# 09-DPLL-3.net
KiCad netlist of a schematic drawn in Altium Designer
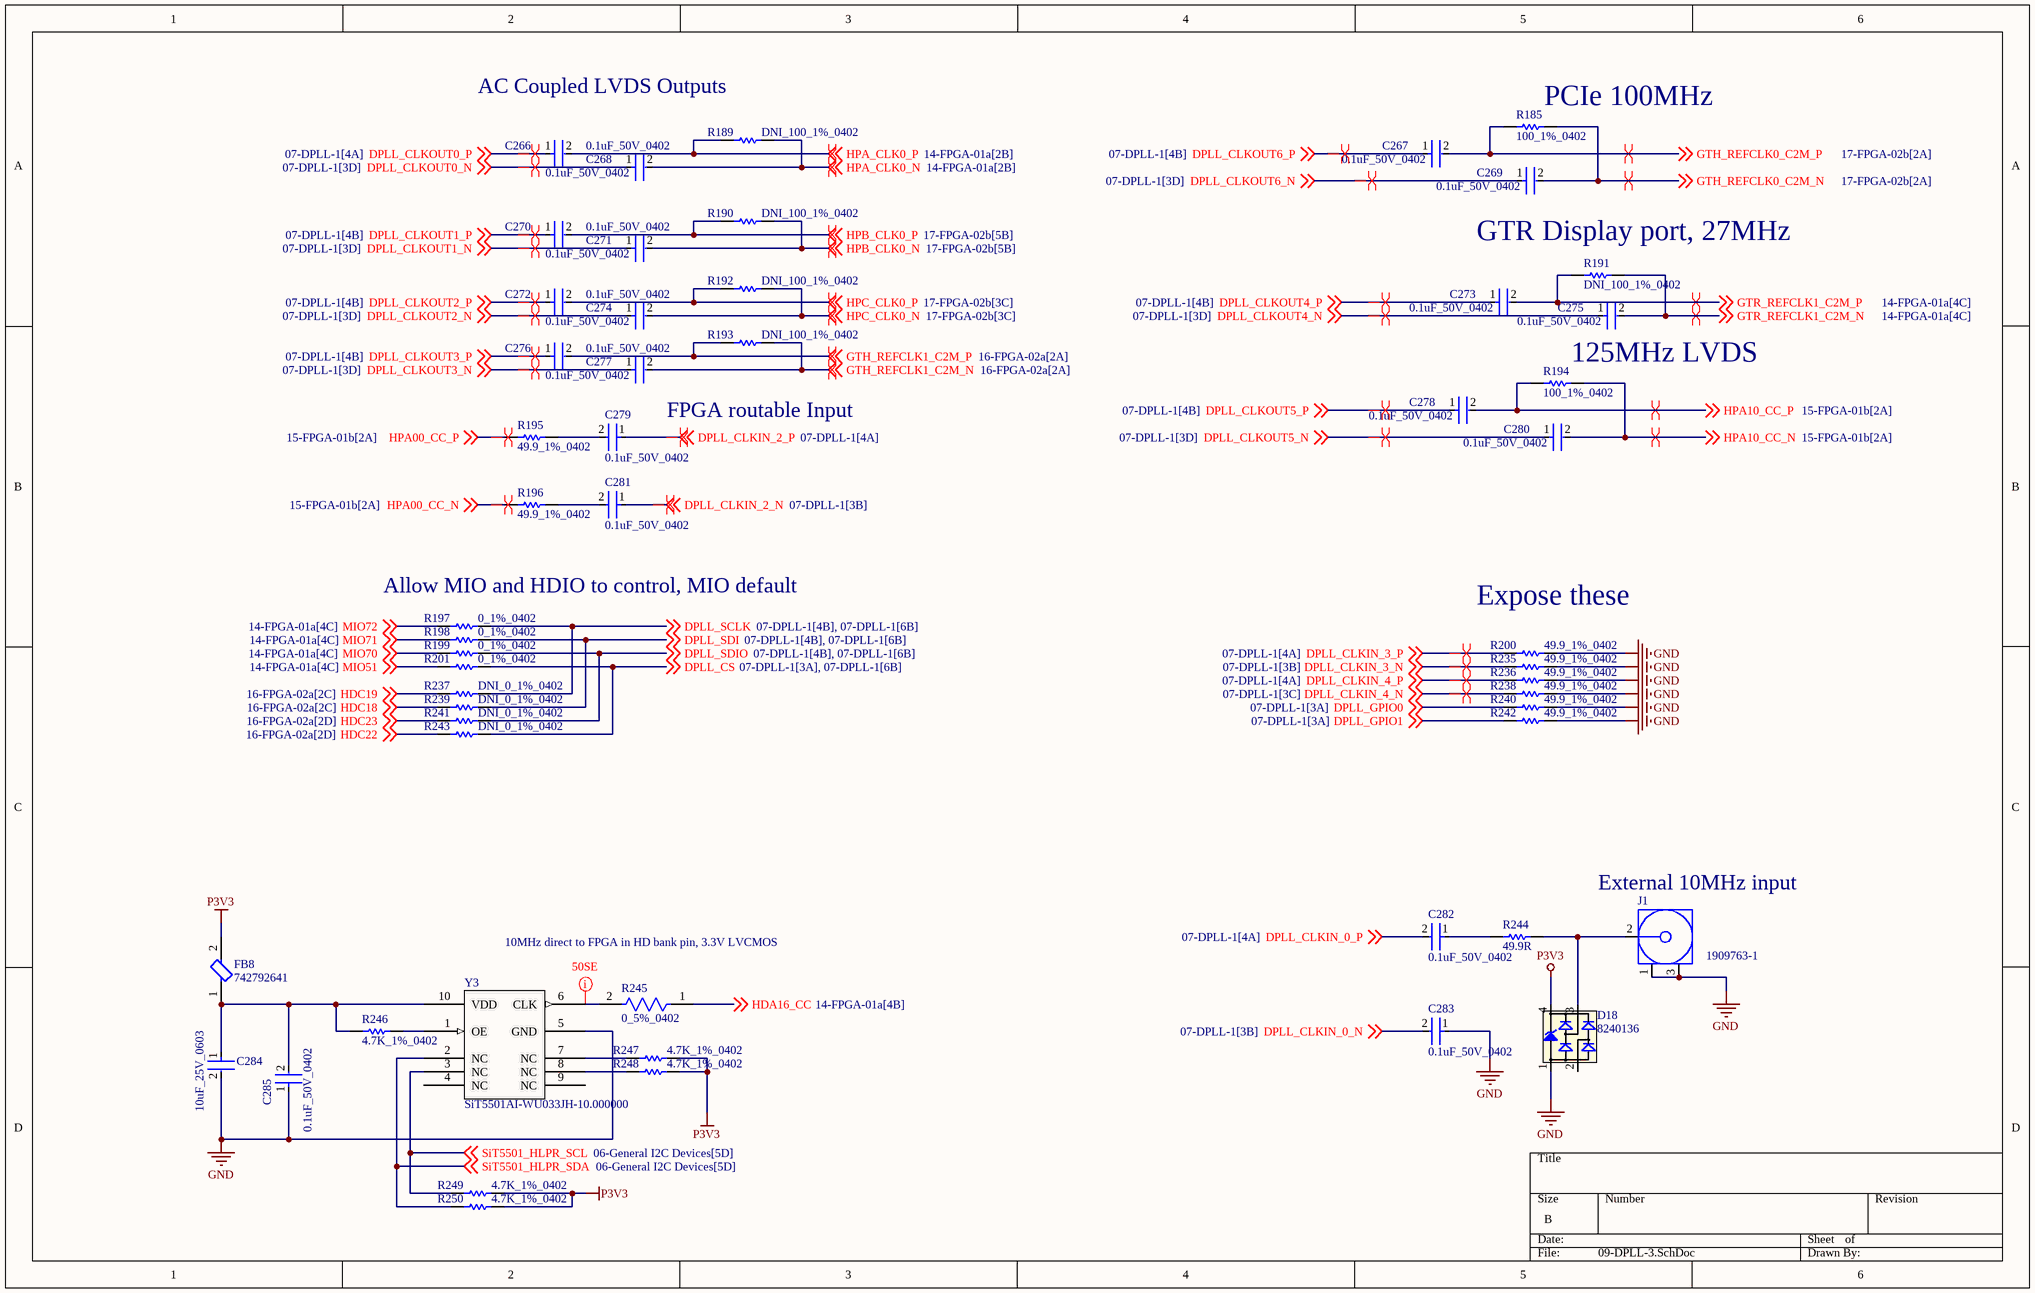
[diagram p0: 09-DPLL-3.SchDoc]

(export (version "E")
  (design (tool "Eeschema 10.0.6"))
  (components
    (comp (ref "C266")
      (value "0.1uF_50V_0402")
      (footprint "FP-C1005-050-0_05-IPC_C")
      (description "Multilayer Ceramic Capacitors 100nF ±10% 50V X7R SMD 0402")
      (fields (field (name "VOLTAGE") "50V") (field (name "TOLERANCE") "10%"))
      (libsource (lib "Altium Content Vault") (part "b4654b650e69147ec39a6b967a45e02"))
    )
    (comp (ref "C267")
      (value "0.1uF_50V_0402")
      (footprint "FP-C1005-050-0_05-IPC_C")
      (description "Multilayer Ceramic Capacitors 100nF ±10% 50V X7R SMD 0402")
      (fields (field (name "VOLTAGE") "50V") (field (name "TOLERANCE") "10%"))
      (libsource (lib "Altium Content Vault") (part "b4654b650e69147ec39a6b967a45e02"))
    )
    (comp (ref "C268")
      (value "0.1uF_50V_0402")
      (footprint "FP-C1005-050-0_05-IPC_C")
      (description "Multilayer Ceramic Capacitors 100nF ±10% 50V X7R SMD 0402")
      (fields (field (name "VOLTAGE") "50V") (field (name "TOLERANCE") "10%"))
      (libsource (lib "Altium Content Vault") (part "b4654b650e69147ec39a6b967a45e02"))
    )
    (comp (ref "C269")
      (value "0.1uF_50V_0402")
      (footprint "FP-C1005-050-0_05-IPC_C")
      (description "Multilayer Ceramic Capacitors 100nF ±10% 50V X7R SMD 0402")
      (fields (field (name "VOLTAGE") "50V") (field (name "TOLERANCE") "10%"))
      (libsource (lib "Altium Content Vault") (part "b4654b650e69147ec39a6b967a45e02"))
    )
    (comp (ref "C270")
      (value "0.1uF_50V_0402")
      (footprint "FP-C1005-050-0_05-IPC_C")
      (description "Multilayer Ceramic Capacitors 100nF ±10% 50V X7R SMD 0402")
      (fields (field (name "VOLTAGE") "50V") (field (name "TOLERANCE") "10%"))
      (libsource (lib "Altium Content Vault") (part "b4654b650e69147ec39a6b967a45e02"))
    )
    (comp (ref "C271")
      (value "0.1uF_50V_0402")
      (footprint "FP-C1005-050-0_05-IPC_C")
      (description "Multilayer Ceramic Capacitors 100nF ±10% 50V X7R SMD 0402")
      (fields (field (name "VOLTAGE") "50V") (field (name "TOLERANCE") "10%"))
      (libsource (lib "Altium Content Vault") (part "b4654b650e69147ec39a6b967a45e02"))
    )
    (comp (ref "C272")
      (value "0.1uF_50V_0402")
      (footprint "FP-C1005-050-0_05-IPC_C")
      (description "Multilayer Ceramic Capacitors 100nF ±10% 50V X7R SMD 0402")
      (fields (field (name "VOLTAGE") "50V") (field (name "TOLERANCE") "10%"))
      (libsource (lib "Altium Content Vault") (part "b4654b650e69147ec39a6b967a45e02"))
    )
    (comp (ref "C273")
      (value "0.1uF_50V_0402")
      (footprint "FP-C1005-050-0_05-IPC_C")
      (description "Multilayer Ceramic Capacitors 100nF ±10% 50V X7R SMD 0402")
      (fields (field (name "VOLTAGE") "50V") (field (name "TOLERANCE") "10%"))
      (libsource (lib "Altium Content Vault") (part "b4654b650e69147ec39a6b967a45e02"))
    )
    (comp (ref "C274")
      (value "0.1uF_50V_0402")
      (footprint "FP-C1005-050-0_05-IPC_C")
      (description "Multilayer Ceramic Capacitors 100nF ±10% 50V X7R SMD 0402")
      (fields (field (name "VOLTAGE") "50V") (field (name "TOLERANCE") "10%"))
      (libsource (lib "Altium Content Vault") (part "b4654b650e69147ec39a6b967a45e02"))
    )
    (comp (ref "C275")
      (value "0.1uF_50V_0402")
      (footprint "FP-C1005-050-0_05-IPC_C")
      (description "Multilayer Ceramic Capacitors 100nF ±10% 50V X7R SMD 0402")
      (fields (field (name "VOLTAGE") "50V") (field (name "TOLERANCE") "10%"))
      (libsource (lib "Altium Content Vault") (part "b4654b650e69147ec39a6b967a45e02"))
    )
    (comp (ref "C276")
      (value "0.1uF_50V_0402")
      (footprint "FP-C1005-050-0_05-IPC_C")
      (description "Multilayer Ceramic Capacitors 100nF ±10% 50V X7R SMD 0402")
      (fields (field (name "VOLTAGE") "50V") (field (name "TOLERANCE") "10%"))
      (libsource (lib "Altium Content Vault") (part "b4654b650e69147ec39a6b967a45e02"))
    )
    (comp (ref "C277")
      (value "0.1uF_50V_0402")
      (footprint "FP-C1005-050-0_05-IPC_C")
      (description "Multilayer Ceramic Capacitors 100nF ±10% 50V X7R SMD 0402")
      (fields (field (name "VOLTAGE") "50V") (field (name "TOLERANCE") "10%"))
      (libsource (lib "Altium Content Vault") (part "b4654b650e69147ec39a6b967a45e02"))
    )
    (comp (ref "C278")
      (value "0.1uF_50V_0402")
      (footprint "FP-C1005-050-0_05-IPC_C")
      (description "Multilayer Ceramic Capacitors 100nF ±10% 50V X7R SMD 0402")
      (fields (field (name "VOLTAGE") "50V") (field (name "TOLERANCE") "10%"))
      (libsource (lib "Altium Content Vault") (part "b4654b650e69147ec39a6b967a45e02"))
    )
    (comp (ref "C279")
      (value "0.1uF_50V_0402")
      (footprint "FP-C1005-050-0_05-IPC_C")
      (description "Multilayer Ceramic Capacitors 100nF ±10% 50V X7R SMD 0402")
      (fields (field (name "VOLTAGE") "50V") (field (name "TOLERANCE") "10%"))
      (libsource (lib "Altium Content Vault") (part "b4654b650e69147ec39a6b967a45e02"))
    )
    (comp (ref "C280")
      (value "0.1uF_50V_0402")
      (footprint "FP-C1005-050-0_05-IPC_C")
      (description "Multilayer Ceramic Capacitors 100nF ±10% 50V X7R SMD 0402")
      (fields (field (name "VOLTAGE") "50V") (field (name "TOLERANCE") "10%"))
      (libsource (lib "Altium Content Vault") (part "b4654b650e69147ec39a6b967a45e02"))
    )
    (comp (ref "C281")
      (value "0.1uF_50V_0402")
      (footprint "FP-C1005-050-0_05-IPC_C")
      (description "Multilayer Ceramic Capacitors 100nF ±10% 50V X7R SMD 0402")
      (fields (field (name "VOLTAGE") "50V") (field (name "TOLERANCE") "10%"))
      (libsource (lib "Altium Content Vault") (part "b4654b650e69147ec39a6b967a45e02"))
    )
    (comp (ref "C282")
      (value "0.1uF_50V_0402")
      (footprint "FP-C1005-050-0_05-IPC_C")
      (description "Multilayer Ceramic Capacitors 100nF ±10% 50V X7R SMD 0402")
      (fields (field (name "VOLTAGE") "50V") (field (name "TOLERANCE") "10%"))
      (libsource (lib "Altium Content Vault") (part "b4654b650e69147ec39a6b967a45e02"))
    )
    (comp (ref "C283")
      (value "0.1uF_50V_0402")
      (footprint "FP-C1005-050-0_05-IPC_C")
      (description "Multilayer Ceramic Capacitors 100nF ±10% 50V X7R SMD 0402")
      (fields (field (name "VOLTAGE") "50V") (field (name "TOLERANCE") "10%"))
      (libsource (lib "Altium Content Vault") (part "b4654b650e69147ec39a6b967a45e02"))
    )
    (comp (ref "C284")
      (value "10uF_25V_0603")
      (footprint "FP-CL10-IPC_C")
      (description "Cap Ceramic 10uF 25V X5R ±20% Pad SMD 0603 +85°C T/R")
      (fields (field (name "TOLERANCE") "20%"))
      (libsource (lib "Altium Content Vault") (part "b4654b650e69147ec39a6b967a45e02"))
    )
    (comp (ref "C285")
      (value "0.1uF_50V_0402")
      (footprint "FP-C1005-050-0_05-IPC_C")
      (description "Multilayer Ceramic Capacitors 100nF ±10% 50V X7R SMD 0402")
      (fields (field (name "VOLTAGE") "50V") (field (name "TOLERANCE") "10%"))
      (libsource (lib "Altium Content Vault") (part "b4654b650e69147ec39a6b967a45e02"))
    )
    (comp (ref "D18")
      (value "8240136")
      (footprint "SOT143-4L")
      (description "TVS Diode WE-TVS-HS, VRWM=3.3V")
      (fields (field (name "MANUFACTURER") "Wuerth Elektronik"))
      (libsource (lib "Altium Content Vault") (part "WE-TVS-HS-4"))
    )
    (comp (ref "FB8")
      (value "742792641")
      (footprint "FP-742792641-MFG")
      (description "FERRITE BEAD 300 OHM 0603 1LN")
      (fields (field (name "TOLERANCE") "25%"))
      (libsource (lib "Altium Content Vault") (part "5f30dd21d616792df468990f7003faa"))
    )
    (comp (ref "J1")
      (value "1909763-1")
      (footprint "TECO-1909763-1_V")
      (description "Ultra Miniature Coaxial Connector Jack, 60 V, 50 Ohm, -40 to 90 degC, RoHS, Tape and Reel")
      (fields (field (name "MANUFACTURER") "TE Connectivity"))
      (libsource (lib "Altium Content Vault") (part "CN-1P-M-RF3"))
    )
    (comp (ref "R185")
      (value "100_1%_0402")
      (footprint "RESC1005X40X25ML05T10")
      (fields (field (name "PART NUMBER") "ERJ-U02F1000X") (field (name "MANUFACTURER") "Panasonic"))
      (libsource (lib "Altium Content Vault") (part "RES"))
    )
    (comp (ref "R189")
      (value "DNI_100_1%_0402")
      (footprint "RESC1005X40X25LL05T05")
      (description "Chip Resistor, 100 Ohm, +/- 1%, 100 mW, -55 to 155 degC, 0402 (1005 Metric), RoHS, Tape and Reel")
      (fields (field (name "MANUFACTURER") "Basic Passives") (field (name "TOLERANCE") "1%"))
      (libsource (lib "Altium Content Vault") (part "RES-2"))
    )
    (comp (ref "R190")
      (value "DNI_100_1%_0402")
      (footprint "RESC1005X40X25LL05T05")
      (description "Chip Resistor, 100 Ohm, +/- 1%, 100 mW, -55 to 155 degC, 0402 (1005 Metric), RoHS, Tape and Reel")
      (fields (field (name "MANUFACTURER") "Basic Passives") (field (name "TOLERANCE") "1%"))
      (libsource (lib "Altium Content Vault") (part "RES-2"))
    )
    (comp (ref "R191")
      (value "DNI_100_1%_0402")
      (footprint "RESC1005X40X25ML05T10")
      (fields (field (name "PART NUMBER") "ERJ-U02F1000X") (field (name "MANUFACTURER") "Panasonic"))
      (libsource (lib "Altium Content Vault") (part "RES"))
    )
    (comp (ref "R192")
      (value "DNI_100_1%_0402")
      (footprint "RESC1005X40X25LL05T05")
      (description "Chip Resistor, 100 Ohm, +/- 1%, 100 mW, -55 to 155 degC, 0402 (1005 Metric), RoHS, Tape and Reel")
      (fields (field (name "MANUFACTURER") "Basic Passives") (field (name "TOLERANCE") "1%"))
      (libsource (lib "Altium Content Vault") (part "RES-2"))
    )
    (comp (ref "R193")
      (value "DNI_100_1%_0402")
      (footprint "RESC1005X40X25LL05T05")
      (description "Chip Resistor, 100 Ohm, +/- 1%, 100 mW, -55 to 155 degC, 0402 (1005 Metric), RoHS, Tape and Reel")
      (fields (field (name "MANUFACTURER") "Basic Passives") (field (name "TOLERANCE") "1%"))
      (libsource (lib "Altium Content Vault") (part "RES-2"))
    )
    (comp (ref "R194")
      (value "100_1%_0402")
      (footprint "RESC1005X40X25ML05T10")
      (fields (field (name "PART NUMBER") "ERJ-U02F1000X") (field (name "MANUFACTURER") "Panasonic"))
      (libsource (lib "Altium Content Vault") (part "RES"))
    )
    (comp (ref "R195")
      (value "49.9_1%_0402")
      (footprint "RESC1005X40X25NL10T10")
      (fields (field (name "PART NUMBER") "RK73H1ETTP49R9F") (field (name "MANUFACTURER") "KOA Speer"))
      (libsource (lib "Altium Content Vault") (part "RES"))
    )
    (comp (ref "R196")
      (value "49.9_1%_0402")
      (footprint "RESC1005X40X25NL10T10")
      (fields (field (name "PART NUMBER") "RK73H1ETTP49R9F") (field (name "MANUFACTURER") "KOA Speer"))
      (libsource (lib "Altium Content Vault") (part "RES"))
    )
    (comp (ref "R197")
      (value "0_1%_0402")
      (footprint "RESC1005X40X25LL05T05")
      (description "Chip Resistor, 0 Ohm, 0.1 W, -55 to 155 degC, 0402 (1005 Metric), RoHS, Tape and Reel")
      (fields (field (name "MANUFACTURER") "Panasonic") (field (name "TOLERANCE") "5%"))
      (libsource (lib "Altium Content Vault") (part "RES-2"))
    )
    (comp (ref "R198")
      (value "0_1%_0402")
      (footprint "RESC1005X40X25LL05T05")
      (description "Chip Resistor, 0 Ohm, 0.1 W, -55 to 155 degC, 0402 (1005 Metric), RoHS, Tape and Reel")
      (fields (field (name "MANUFACTURER") "Panasonic") (field (name "TOLERANCE") "5%"))
      (libsource (lib "Altium Content Vault") (part "RES-2"))
    )
    (comp (ref "R199")
      (value "0_1%_0402")
      (footprint "RESC1005X40X25LL05T05")
      (description "Chip Resistor, 0 Ohm, 0.1 W, -55 to 155 degC, 0402 (1005 Metric), RoHS, Tape and Reel")
      (fields (field (name "MANUFACTURER") "Panasonic") (field (name "TOLERANCE") "5%"))
      (libsource (lib "Altium Content Vault") (part "RES-2"))
    )
    (comp (ref "R200")
      (value "49.9_1%_0402")
      (footprint "RESC1005X40X25NL10T10")
      (fields (field (name "PART NUMBER") "RK73H1ETTP49R9F") (field (name "MANUFACTURER") "KOA Speer"))
      (libsource (lib "Altium Content Vault") (part "RES"))
    )
    (comp (ref "R201")
      (value "0_1%_0402")
      (footprint "RESC1005X40X25LL05T05")
      (description "Chip Resistor, 0 Ohm, 0.1 W, -55 to 155 degC, 0402 (1005 Metric), RoHS, Tape and Reel")
      (fields (field (name "MANUFACTURER") "Panasonic") (field (name "TOLERANCE") "5%"))
      (libsource (lib "Altium Content Vault") (part "RES-2"))
    )
    (comp (ref "R235")
      (value "49.9_1%_0402")
      (footprint "RESC1005X40X25NL10T10")
      (fields (field (name "PART NUMBER") "RK73H1ETTP49R9F") (field (name "MANUFACTURER") "KOA Speer"))
      (libsource (lib "Altium Content Vault") (part "RES"))
    )
    (comp (ref "R236")
      (value "49.9_1%_0402")
      (footprint "RESC1005X40X25NL10T10")
      (fields (field (name "PART NUMBER") "RK73H1ETTP49R9F") (field (name "MANUFACTURER") "KOA Speer"))
      (libsource (lib "Altium Content Vault") (part "RES"))
    )
    (comp (ref "R237")
      (value "DNI_0_1%_0402")
      (footprint "RESC1005X40X25LL05T05")
      (description "Chip Resistor, 0 Ohm, 0.1 W, -55 to 155 degC, 0402 (1005 Metric), RoHS, Tape and Reel")
      (fields (field (name "MANUFACTURER") "Panasonic") (field (name "TOLERANCE") "5%"))
      (libsource (lib "Altium Content Vault") (part "RES-2"))
    )
    (comp (ref "R238")
      (value "49.9_1%_0402")
      (footprint "RESC1005X40X25NL10T10")
      (fields (field (name "PART NUMBER") "RK73H1ETTP49R9F") (field (name "MANUFACTURER") "KOA Speer"))
      (libsource (lib "Altium Content Vault") (part "RES"))
    )
    (comp (ref "R239")
      (value "DNI_0_1%_0402")
      (footprint "RESC1005X40X25LL05T05")
      (description "Chip Resistor, 0 Ohm, 0.1 W, -55 to 155 degC, 0402 (1005 Metric), RoHS, Tape and Reel")
      (fields (field (name "MANUFACTURER") "Panasonic") (field (name "TOLERANCE") "5%"))
      (libsource (lib "Altium Content Vault") (part "RES-2"))
    )
    (comp (ref "R240")
      (value "49.9_1%_0402")
      (footprint "RESC1005X40X25NL10T10")
      (fields (field (name "PART NUMBER") "RK73H1ETTP49R9F") (field (name "MANUFACTURER") "KOA Speer"))
      (libsource (lib "Altium Content Vault") (part "RES"))
    )
    (comp (ref "R241")
      (value "DNI_0_1%_0402")
      (footprint "RESC1005X40X25LL05T05")
      (description "Chip Resistor, 0 Ohm, 0.1 W, -55 to 155 degC, 0402 (1005 Metric), RoHS, Tape and Reel")
      (fields (field (name "MANUFACTURER") "Panasonic") (field (name "TOLERANCE") "5%"))
      (libsource (lib "Altium Content Vault") (part "RES-2"))
    )
    (comp (ref "R242")
      (value "49.9_1%_0402")
      (footprint "RESC1005X40X25NL10T10")
      (fields (field (name "PART NUMBER") "RK73H1ETTP49R9F") (field (name "MANUFACTURER") "KOA Speer"))
      (libsource (lib "Altium Content Vault") (part "RES"))
    )
    (comp (ref "R243")
      (value "DNI_0_1%_0402")
      (footprint "RESC1005X40X25LL05T05")
      (description "Chip Resistor, 0 Ohm, 0.1 W, -55 to 155 degC, 0402 (1005 Metric), RoHS, Tape and Reel")
      (fields (field (name "MANUFACTURER") "Panasonic") (field (name "TOLERANCE") "5%"))
      (libsource (lib "Altium Content Vault") (part "RES-2"))
    )
    (comp (ref "R244")
      (value "49.9R")
      (footprint "RESC1608X55X25NL10T15")
      (libsource (lib "Altium Content Vault") (part "RES-2"))
    )
    (comp (ref "R245")
      (value "0_5%_0402")
      (footprint "FP-AC0402-0_37-IPC_B")
      (description "RESISTOR 0402 JUMPER ZERO OHM")
      (fields (field (name "TOLERANCE") "1%"))
      (libsource (lib "Altium Content Vault") (part "1029c3af85768c4190bb7ad29bc67b5"))
    )
    (comp (ref "R246")
      (value "4.7K_1%_0402")
      (footprint "RESC1005X40X25NL10T10")
      (fields (field (name "MANUFACTURER") "Bourns") (field (name "PART NUMBER") "CR0402-FX-4701GLF"))
      (libsource (lib "Altium Content Vault") (part "RES"))
    )
    (comp (ref "R247")
      (value "4.7K_1%_0402")
      (footprint "RESC1005X40X25NL10T10")
      (fields (field (name "MANUFACTURER") "Bourns") (field (name "PART NUMBER") "CR0402-FX-4701GLF"))
      (libsource (lib "Altium Content Vault") (part "RES"))
    )
    (comp (ref "R248")
      (value "4.7K_1%_0402")
      (footprint "RESC1005X40X25NL10T10")
      (fields (field (name "MANUFACTURER") "Bourns") (field (name "PART NUMBER") "CR0402-FX-4701GLF"))
      (libsource (lib "Altium Content Vault") (part "RES"))
    )
    (comp (ref "R249")
      (value "4.7K_1%_0402")
      (footprint "RESC1005X40X25NL10T10")
      (fields (field (name "MANUFACTURER") "Bourns") (field (name "PART NUMBER") "CR0402-FX-4701GLF"))
      (libsource (lib "Altium Content Vault") (part "RES"))
    )
    (comp (ref "R250")
      (value "4.7K_1%_0402")
      (footprint "RESC1005X40X25NL10T10")
      (fields (field (name "MANUFACTURER") "Bourns") (field (name "PART NUMBER") "CR0402-FX-4701GLF"))
      (libsource (lib "Altium Content Vault") (part "RES"))
    )
    (comp (ref "Y3")
      (value "SiTime_SiT5501AC-WU-33E0-10T")
      (footprint "SITIME_SPL-086-CQFN-010-C07050_REV_DRAFT")
      (description "OSC, MEMS, STRATUM 3E, 10.000MHZ, 10PPB STAB, LVCMOS, 3.3V, O/P EN, 7.0X5.0X2.2MM, CQFN-10")
      (fields
        (field (name "MANUFACTURER PART NUMBER") "SiT5501AI-WU033JH-10.000000")
        (field (name "MANUFACTURER") "SiTime")
      )
      (libsource (lib "OCXO_DaughterCard") (part "CMP-OSC-00029-2"))
    )
  )
  (nets
    (net (code "1") (name "DPLL_CLKIN_0_N") (class "Default")
      (node (ref "C283") (pin "2") (pinfunction "2_2") (pintype "passive"))
    )
    (net (code "2") (name "DPLL_CLKIN_0_P") (class "Default")
      (node (ref "C282") (pin "2") (pinfunction "2_2") (pintype "passive"))
    )
    (net (code "3") (name "DPLL_CLKIN_2_N") (class "Default")
      (node (ref "C281") (pin "1") (pinfunction "1_1") (pintype "passive"))
    )
    (net (code "4") (name "DPLL_CLKIN_2_P") (class "Default")
      (node (ref "C279") (pin "1") (pinfunction "1_1") (pintype "passive"))
    )
    (net (code "5") (name "DPLL_CLKIN_3_N") (class "Default")
      (node (ref "R235") (pin "1") (pinfunction "1_1") (pintype "passive"))
    )
    (net (code "6") (name "DPLL_CLKIN_3_P") (class "Default")
      (node (ref "R200") (pin "1") (pinfunction "1_1") (pintype "passive"))
    )
    (net (code "7") (name "DPLL_CLKIN_4_N") (class "Default")
      (node (ref "R238") (pin "1") (pinfunction "1_1") (pintype "passive"))
    )
    (net (code "8") (name "DPLL_CLKIN_4_P") (class "Default")
      (node (ref "R236") (pin "1") (pinfunction "1_1") (pintype "passive"))
    )
    (net (code "9") (name "DPLL_CLKOUT0_N") (class "Default")
      (node (ref "C268") (pin "1") (pinfunction "1_1") (pintype "passive"))
    )
    (net (code "10") (name "DPLL_CLKOUT0_P") (class "Default")
      (node (ref "C266") (pin "1") (pinfunction "1_1") (pintype "passive"))
    )
    (net (code "11") (name "DPLL_CLKOUT1_N") (class "Default")
      (node (ref "C271") (pin "1") (pinfunction "1_1") (pintype "passive"))
    )
    (net (code "12") (name "DPLL_CLKOUT1_P") (class "Default")
      (node (ref "C270") (pin "1") (pinfunction "1_1") (pintype "passive"))
    )
    (net (code "13") (name "DPLL_CLKOUT2_N") (class "Default")
      (node (ref "C274") (pin "1") (pinfunction "1_1") (pintype "passive"))
    )
    (net (code "14") (name "DPLL_CLKOUT2_P") (class "Default")
      (node (ref "C272") (pin "1") (pinfunction "1_1") (pintype "passive"))
    )
    (net (code "15") (name "DPLL_CLKOUT3_N") (class "Default")
      (node (ref "C277") (pin "1") (pinfunction "1_1") (pintype "passive"))
    )
    (net (code "16") (name "DPLL_CLKOUT3_P") (class "Default")
      (node (ref "C276") (pin "1") (pinfunction "1_1") (pintype "passive"))
    )
    (net (code "17") (name "DPLL_CLKOUT4_N") (class "Default")
      (node (ref "C275") (pin "1") (pinfunction "1_1") (pintype "passive"))
    )
    (net (code "18") (name "DPLL_CLKOUT4_P") (class "Default")
      (node (ref "C273") (pin "1") (pinfunction "1_1") (pintype "passive"))
    )
    (net (code "19") (name "DPLL_CLKOUT5_N") (class "Default")
      (node (ref "C280") (pin "1") (pinfunction "1_1") (pintype "passive"))
    )
    (net (code "20") (name "DPLL_CLKOUT5_P") (class "Default")
      (node (ref "C278") (pin "1") (pinfunction "1_1") (pintype "passive"))
    )
    (net (code "21") (name "DPLL_CLKOUT6_N") (class "Default")
      (node (ref "C269") (pin "1") (pinfunction "1_1") (pintype "passive"))
    )
    (net (code "22") (name "DPLL_CLKOUT6_P") (class "Default")
      (node (ref "C267") (pin "1") (pinfunction "1_1") (pintype "passive"))
    )
    (net (code "23") (name "DPLL_CS") (class "Default")
      (node (ref "R201") (pin "2") (pinfunction "2_2") (pintype "passive"))
      (node (ref "R243") (pin "2") (pinfunction "2_2") (pintype "passive"))
    )
    (net (code "24") (name "DPLL_GPIO0") (class "Default")
      (node (ref "R240") (pin "1") (pinfunction "1_1") (pintype "passive"))
    )
    (net (code "25") (name "DPLL_GPIO1") (class "Default")
      (node (ref "R242") (pin "1") (pinfunction "1_1") (pintype "passive"))
    )
    (net (code "26") (name "DPLL_SCLK") (class "Default")
      (node (ref "R197") (pin "2") (pinfunction "2_2") (pintype "passive"))
      (node (ref "R237") (pin "2") (pinfunction "2_2") (pintype "passive"))
    )
    (net (code "27") (name "DPLL_SDI") (class "Default")
      (node (ref "R198") (pin "2") (pinfunction "2_2") (pintype "passive"))
      (node (ref "R239") (pin "2") (pinfunction "2_2") (pintype "passive"))
    )
    (net (code "28") (name "DPLL_SDIO") (class "Default")
      (node (ref "R199") (pin "2") (pinfunction "2_2") (pintype "passive"))
      (node (ref "R241") (pin "2") (pinfunction "2_2") (pintype "passive"))
    )
    (net (code "29") (name "GND") (class "Default")
      (node (ref "C283") (pin "1") (pinfunction "1_1") (pintype "passive"))
      (node (ref "C284") (pin "2") (pinfunction "2_2") (pintype "passive"))
      (node (ref "C285") (pin "1") (pinfunction "1_1") (pintype "passive"))
      (node (ref "D18") (pin "1") (pinfunction "GND_1") (pintype "passive"))
      (node (ref "J1") (pin "1") (pinfunction "1_1") (pintype "passive"))
      (node (ref "J1") (pin "3") (pinfunction "3_3") (pintype "passive"))
      (node (ref "R200") (pin "2") (pinfunction "2_2") (pintype "passive"))
      (node (ref "R235") (pin "2") (pinfunction "2_2") (pintype "passive"))
      (node (ref "R236") (pin "2") (pinfunction "2_2") (pintype "passive"))
      (node (ref "R238") (pin "2") (pinfunction "2_2") (pintype "passive"))
      (node (ref "R240") (pin "2") (pinfunction "2_2") (pintype "passive"))
      (node (ref "R242") (pin "2") (pinfunction "2_2") (pintype "passive"))
      (node (ref "Y3") (pin "5") (pinfunction "GND_5") (pintype "power_in"))
    )
    (net (code "30") (name "GTH_REFCLK0_C2M_N") (class "Default")
      (node (ref "C269") (pin "2") (pinfunction "2_2") (pintype "passive"))
      (node (ref "R185") (pin "2") (pinfunction "2_2") (pintype "passive"))
    )
    (net (code "31") (name "GTH_REFCLK0_C2M_P") (class "Default")
      (node (ref "C267") (pin "2") (pinfunction "2_2") (pintype "passive"))
      (node (ref "R185") (pin "1") (pinfunction "1_1") (pintype "passive"))
    )
    (net (code "32") (name "GTH_REFCLK1_C2M_N") (class "Default")
      (node (ref "C277") (pin "2") (pinfunction "2_2") (pintype "passive"))
      (node (ref "R193") (pin "2") (pinfunction "2_2") (pintype "passive"))
    )
    (net (code "33") (name "GTH_REFCLK1_C2M_P") (class "Default")
      (node (ref "C276") (pin "2") (pinfunction "2_2") (pintype "passive"))
      (node (ref "R193") (pin "1") (pinfunction "1_1") (pintype "passive"))
    )
    (net (code "34") (name "GTR_REFCLK1_C2M_N") (class "Default")
      (node (ref "C275") (pin "2") (pinfunction "2_2") (pintype "passive"))
      (node (ref "R191") (pin "2") (pinfunction "2_2") (pintype "passive"))
    )
    (net (code "35") (name "GTR_REFCLK1_C2M_P") (class "Default")
      (node (ref "C273") (pin "2") (pinfunction "2_2") (pintype "passive"))
      (node (ref "R191") (pin "1") (pinfunction "1_1") (pintype "passive"))
    )
    (net (code "36") (name "HDA16_CC") (class "Default")
      (node (ref "R245") (pin "1") (pinfunction "1_1") (pintype "passive"))
    )
    (net (code "37") (name "HDC18") (class "Default")
      (node (ref "R239") (pin "1") (pinfunction "1_1") (pintype "passive"))
    )
    (net (code "38") (name "HDC19") (class "Default")
      (node (ref "R237") (pin "1") (pinfunction "1_1") (pintype "passive"))
    )
    (net (code "39") (name "HDC22") (class "Default")
      (node (ref "R243") (pin "1") (pinfunction "1_1") (pintype "passive"))
    )
    (net (code "40") (name "HDC23") (class "Default")
      (node (ref "R241") (pin "1") (pinfunction "1_1") (pintype "passive"))
    )
    (net (code "41") (name "HPA00_CC_N") (class "Default")
      (node (ref "R196") (pin "1") (pinfunction "1_1") (pintype "passive"))
    )
    (net (code "42") (name "HPA00_CC_P") (class "Default")
      (node (ref "R195") (pin "1") (pinfunction "1_1") (pintype "passive"))
    )
    (net (code "43") (name "HPA10_CC_N") (class "Default")
      (node (ref "C280") (pin "2") (pinfunction "2_2") (pintype "passive"))
      (node (ref "R194") (pin "2") (pinfunction "2_2") (pintype "passive"))
    )
    (net (code "44") (name "HPA10_CC_P") (class "Default")
      (node (ref "C278") (pin "2") (pinfunction "2_2") (pintype "passive"))
      (node (ref "R194") (pin "1") (pinfunction "1_1") (pintype "passive"))
    )
    (net (code "45") (name "HPA_CLK0_N") (class "Default")
      (node (ref "C268") (pin "2") (pinfunction "2_2") (pintype "passive"))
      (node (ref "R189") (pin "2") (pinfunction "2_2") (pintype "passive"))
    )
    (net (code "46") (name "HPA_CLK0_P") (class "Default")
      (node (ref "C266") (pin "2") (pinfunction "2_2") (pintype "passive"))
      (node (ref "R189") (pin "1") (pinfunction "1_1") (pintype "passive"))
    )
    (net (code "47") (name "HPB_CLK0_N") (class "Default")
      (node (ref "C271") (pin "2") (pinfunction "2_2") (pintype "passive"))
      (node (ref "R190") (pin "2") (pinfunction "2_2") (pintype "passive"))
    )
    (net (code "48") (name "HPB_CLK0_P") (class "Default")
      (node (ref "C270") (pin "2") (pinfunction "2_2") (pintype "passive"))
      (node (ref "R190") (pin "1") (pinfunction "1_1") (pintype "passive"))
    )
    (net (code "49") (name "HPC_CLK0_N") (class "Default")
      (node (ref "C274") (pin "2") (pinfunction "2_2") (pintype "passive"))
      (node (ref "R192") (pin "2") (pinfunction "2_2") (pintype "passive"))
    )
    (net (code "50") (name "HPC_CLK0_P") (class "Default")
      (node (ref "C272") (pin "2") (pinfunction "2_2") (pintype "passive"))
      (node (ref "R192") (pin "1") (pinfunction "1_1") (pintype "passive"))
    )
    (net (code "51") (name "MIO51") (class "Default")
      (node (ref "R201") (pin "1") (pinfunction "1_1") (pintype "passive"))
    )
    (net (code "52") (name "MIO70") (class "Default")
      (node (ref "R199") (pin "1") (pinfunction "1_1") (pintype "passive"))
    )
    (net (code "53") (name "MIO71") (class "Default")
      (node (ref "R198") (pin "1") (pinfunction "1_1") (pintype "passive"))
    )
    (net (code "54") (name "MIO72") (class "Default")
      (node (ref "R197") (pin "1") (pinfunction "1_1") (pintype "passive"))
    )
    (net (code "55") (name "Net-(C279-Pad2)") (class "Default")
      (node (ref "C279") (pin "2") (pinfunction "2_2") (pintype "passive"))
      (node (ref "R195") (pin "2") (pinfunction "2_2") (pintype "passive"))
    )
    (net (code "56") (name "Net-(C281-Pad2)") (class "Default")
      (node (ref "C281") (pin "2") (pinfunction "2_2") (pintype "passive"))
      (node (ref "R196") (pin "2") (pinfunction "2_2") (pintype "passive"))
    )
    (net (code "57") (name "Net-(C282-Pad1)") (class "Default")
      (node (ref "C282") (pin "1") (pinfunction "1_1") (pintype "passive"))
      (node (ref "R244") (pin "1") (pinfunction "1_1") (pintype "passive"))
    )
    (net (code "58") (name "Net-(D18-I{slash}O2)") (class "Default")
      (node (ref "D18") (pin "3") (pinfunction "I/O2_3") (pintype "passive"))
      (node (ref "J1") (pin "2") (pinfunction "2_2") (pintype "passive"))
      (node (ref "R244") (pin "2") (pinfunction "2_2") (pintype "passive"))
    )
    (net (code "59") (name "Net-(R247-Pad1)") (class "Default")
      (node (ref "R247") (pin "1") (pinfunction "1_1") (pintype "passive"))
      (node (ref "Y3") (pin "7") (pinfunction "NC_7") (pintype "passive"))
    )
    (net (code "60") (name "Net-(R248-Pad1)") (class "Default")
      (node (ref "R248") (pin "1") (pinfunction "1_1") (pintype "passive"))
      (node (ref "Y3") (pin "8") (pinfunction "NC_8") (pintype "passive"))
    )
    (net (code "61") (name "Net-(Y3-CLK)") (class "Default")
      (node (ref "R245") (pin "2") (pinfunction "2_2") (pintype "passive"))
      (node (ref "Y3") (pin "6") (pinfunction "CLK_6") (pintype "output"))
    )
    (net (code "62") (name "Net-(Y3-OE)") (class "Default")
      (node (ref "R246") (pin "1") (pinfunction "1_1") (pintype "passive"))
      (node (ref "Y3") (pin "1") (pinfunction "OE_1") (pintype "input"))
    )
    (net (code "63") (name "Net-(Y3-VDD)") (class "Default")
      (node (ref "C284") (pin "1") (pinfunction "1_1") (pintype "passive"))
      (node (ref "C285") (pin "2") (pinfunction "2_2") (pintype "passive"))
      (node (ref "FB8") (pin "1") (pinfunction "1_1") (pintype "passive"))
      (node (ref "R246") (pin "2") (pinfunction "2_2") (pintype "passive"))
      (node (ref "Y3") (pin "10") (pinfunction "VDD_10") (pintype "power_in"))
    )
    (net (code "64") (name "P3V3") (class "Default")
      (node (ref "D18") (pin "4") (pinfunction "VDD_4") (pintype "passive"))
      (node (ref "FB8") (pin "2") (pinfunction "2_2") (pintype "passive"))
      (node (ref "R247") (pin "2") (pinfunction "2_2") (pintype "passive"))
      (node (ref "R248") (pin "2") (pinfunction "2_2") (pintype "passive"))
      (node (ref "R249") (pin "2") (pinfunction "2_2") (pintype "passive"))
      (node (ref "R250") (pin "2") (pinfunction "2_2") (pintype "passive"))
    )
    (net (code "65") (name "SiT5501_HLPR_SCL") (class "Default")
      (node (ref "R249") (pin "1") (pinfunction "1_1") (pintype "passive"))
      (node (ref "Y3") (pin "3") (pinfunction "NC_3") (pintype "passive"))
    )
    (net (code "66") (name "SiT5501_HLPR_SDA") (class "Default")
      (node (ref "R250") (pin "1") (pinfunction "1_1") (pintype "passive"))
      (node (ref "Y3") (pin "2") (pinfunction "NC_2") (pintype "passive"))
    )
    (net (code "67") (name "unconnected-(D18-I{slash}O1-Pad2)") (class "Default")
      (node (ref "D18") (pin "2") (pinfunction "I/O1_2") (pintype "passive"))
    )
    (net (code "68") (name "unconnected-(Y3-NC-Pad4)") (class "Default")
      (node (ref "Y3") (pin "4") (pinfunction "NC_4") (pintype "passive"))
    )
    (net (code "69") (name "unconnected-(Y3-NC-Pad9)") (class "Default")
      (node (ref "Y3") (pin "9") (pinfunction "NC_9") (pintype "passive"))
    )
  )
)
